# Fujin_Main.net
KiCad netlist of a schematic drawn in Altium Designer
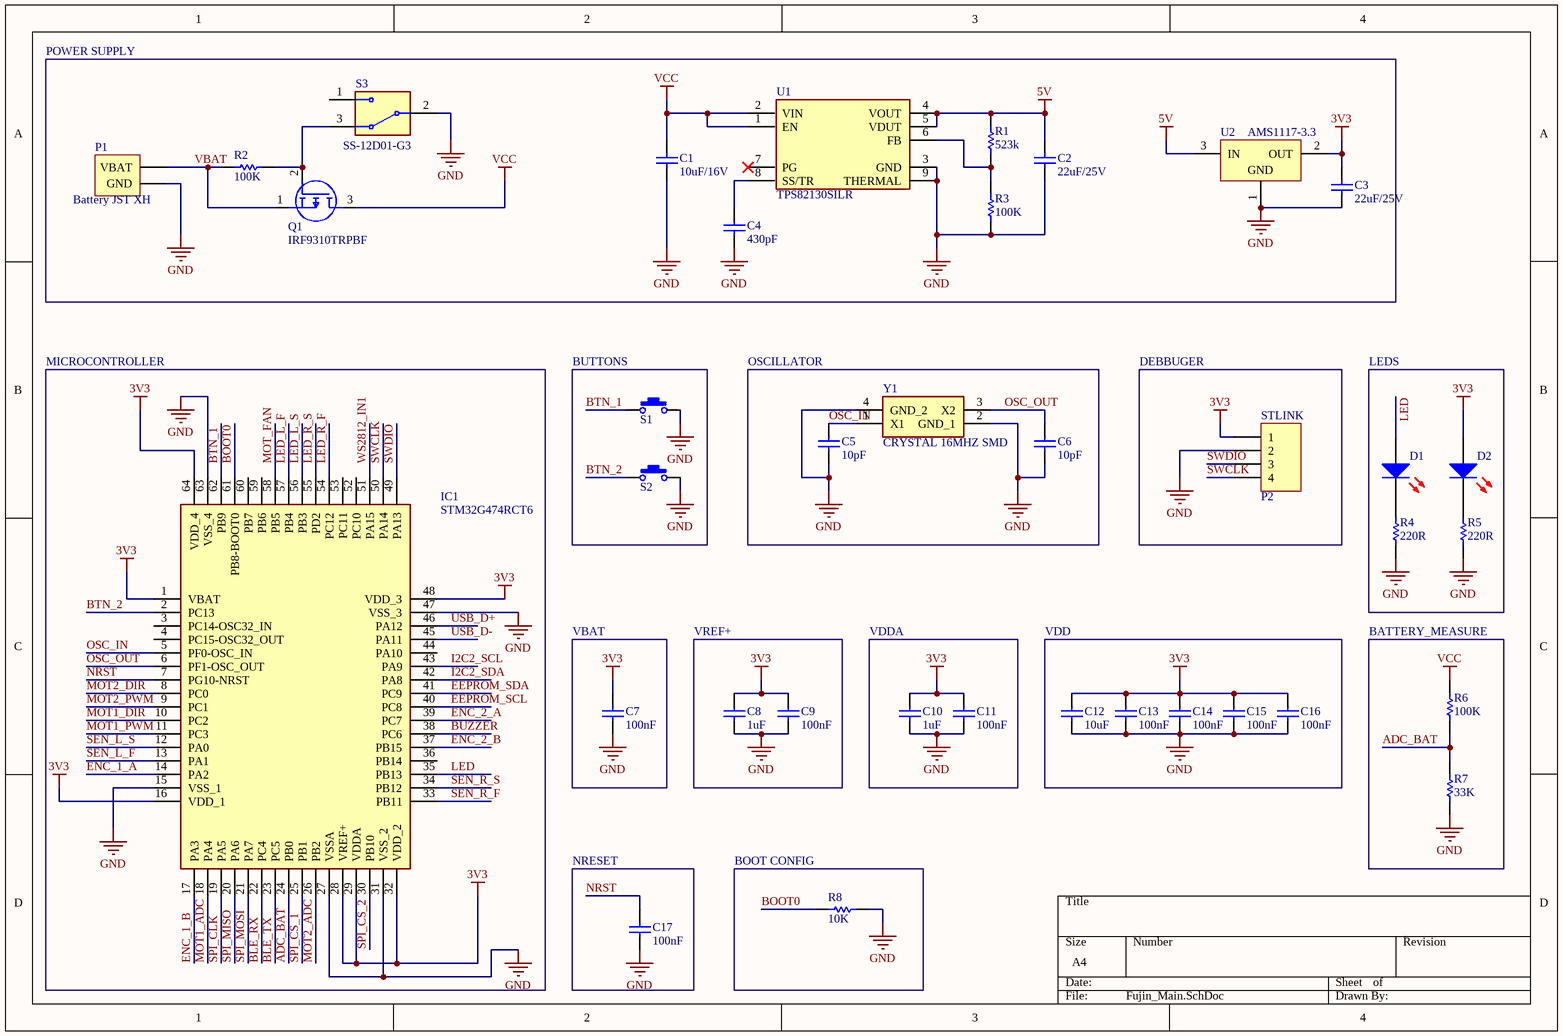
[diagram p0: Fujin_Main.SchDoc]

(export (version "E")
  (design (tool "Eeschema 10.0.6"))
  (components
    (comp (ref "C1")
      (value "10uF/16V")
      (footprint "CAPACITOR-0805")
      (description "CAP CER 10UF 16V X5R 0805")
      (fields
        (field (name "MANUFACTURER") "AVX Corporation")
        (field (name "MANUFACTURER PART NUMBER") "0805YD106KAT2A")
      )
      (libsource (lib "FujinLib") (part "CAP CER 10UF 16V X5R 0805"))
    )
    (comp (ref "C2")
      (value "22uF/25V")
      (footprint "CAPACITOR-0805")
      (description "CAP CER 22UF 25V X5R 0805")
      (fields
        (field (name "MANUFACTURER") "AVX Corporation")
        (field (name "MANUFACTURER PART NUMBER") "0805YD106KAT2A")
      )
      (libsource (lib "FujinLib") (part "CAP CER 22UF 25V X5R 0805"))
    )
    (comp (ref "C3")
      (value "22uF/25V")
      (footprint "CAPACITOR-0805")
      (description "CAP CER 22UF 25V X5R 0805")
      (fields
        (field (name "MANUFACTURER") "AVX Corporation")
        (field (name "MANUFACTURER PART NUMBER") "0805YD106KAT2A")
      )
      (libsource (lib "FujinLib") (part "CAP CER 22UF 25V X5R 0805"))
    )
    (comp (ref "C4")
      (value "430pF")
      (footprint "Capacitor-0603")
      (description "Capacitor Cer 430pF")
      (fields (field (name "MANUFACTURER PART NUMBER") "IMP14925"))
      (libsource (lib "FujinLib") (part "CAP 430pF"))
    )
    (comp (ref "C5")
      (value "10pF")
      (footprint "CAP 0402")
      (description "Capacitor Cer 10pF")
      (fields (field (name "MANUFACTURER PART NUMBER") "IMP14925"))
      (libsource (lib "FujinLib") (part "CAP 10pF"))
    )
    (comp (ref "C6")
      (value "10pF")
      (footprint "CAP 0402")
      (description "Capacitor Cer 10pF")
      (fields (field (name "MANUFACTURER PART NUMBER") "IMP14925"))
      (libsource (lib "FujinLib") (part "CAP 10pF"))
    )
    (comp (ref "C7")
      (value "100nF")
      (footprint "CAP 0402")
      (description "Capacitor Cer 100nF 50V 0402")
      (fields (field (name "MANUFACTURER PART NUMBER") "IMP14925"))
      (libsource (lib "FujinLib") (part "CAP 100NF 50V 0402"))
    )
    (comp (ref "C8")
      (value "1uF")
      (footprint "Capacitor-0603")
      (description "Multilayer Ceramic Capacitors MLCC - SMD/SMT 1uF 50Volts X5R +/-10% 0603 STD")
      (fields
        (field (name "MANUFACTURER") "Taiyo Yuden")
        (field (name "MANUFACTURER PART NUMBER") "UMK107BJ105KA-T")
      )
      (libsource (lib "FujinLib") (part "CAP CER 1UF 50V 0603"))
    )
    (comp (ref "C9")
      (value "100nF")
      (footprint "CAP 0402")
      (description "Capacitor Cer 100nF 50V 0402")
      (fields (field (name "MANUFACTURER PART NUMBER") "IMP14925"))
      (libsource (lib "FujinLib") (part "CAP 100NF 50V 0402"))
    )
    (comp (ref "C10")
      (value "1uF")
      (footprint "Capacitor-0603")
      (description "Multilayer Ceramic Capacitors MLCC - SMD/SMT 1uF 50Volts X5R +/-10% 0603 STD")
      (fields
        (field (name "MANUFACTURER") "Taiyo Yuden")
        (field (name "MANUFACTURER PART NUMBER") "UMK107BJ105KA-T")
      )
      (libsource (lib "FujinLib") (part "CAP CER 1UF 50V 0603"))
    )
    (comp (ref "C11")
      (value "100nF")
      (footprint "CAP 0402")
      (description "Capacitor Cer 100nF 50V 0402")
      (fields (field (name "MANUFACTURER PART NUMBER") "IMP14925"))
      (libsource (lib "FujinLib") (part "CAP 100NF 50V 0402"))
    )
    (comp (ref "C12")
      (value "10uF")
      (footprint "CAPACITOR-0805")
      (description "CAP CER 10UF 16V X5R 0805")
      (fields
        (field (name "MANUFACTURER") "AVX Corporation")
        (field (name "MANUFACTURER PART NUMBER") "0805YD106KAT2A")
      )
      (libsource (lib "FujinLib") (part "CAP CER 10UF 16V X5R 0805"))
    )
    (comp (ref "C13")
      (value "100nF")
      (footprint "CAP 0402")
      (description "Capacitor Cer 100nF 50V 0402")
      (fields (field (name "MANUFACTURER PART NUMBER") "IMP14925"))
      (libsource (lib "FujinLib") (part "CAP 100NF 50V 0402"))
    )
    (comp (ref "C14")
      (value "100nF")
      (footprint "CAP 0402")
      (description "Capacitor Cer 100nF 50V 0402")
      (fields (field (name "MANUFACTURER PART NUMBER") "IMP14925"))
      (libsource (lib "FujinLib") (part "CAP 100NF 50V 0402"))
    )
    (comp (ref "C15")
      (value "100nF")
      (footprint "CAP 0402")
      (description "Capacitor Cer 100nF 50V 0402")
      (fields (field (name "MANUFACTURER PART NUMBER") "IMP14925"))
      (libsource (lib "FujinLib") (part "CAP 100NF 50V 0402"))
    )
    (comp (ref "C16")
      (value "100nF")
      (footprint "CAP 0402")
      (description "Capacitor Cer 100nF 50V 0402")
      (fields (field (name "MANUFACTURER PART NUMBER") "IMP14925"))
      (libsource (lib "FujinLib") (part "CAP 100NF 50V 0402"))
    )
    (comp (ref "C17")
      (value "100nF")
      (footprint "CAP 0402")
      (description "Capacitor Cer 100nF 50V 0402")
      (fields (field (name "MANUFACTURER PART NUMBER") "IMP14925"))
      (libsource (lib "FujinLib") (part "CAP 100NF 50V 0402"))
    )
    (comp (ref "D1")
      (value "LED RED 0603")
      (footprint "LED 0603")
      (description "LED")
      (fields
        (field (name "MANUFACTURER_PART_NUMBER") "SML-D12U1WT86")
        (field (name "MOUSER PART NUMBER") "755-SML-D12U1WT86")
      )
      (libsource (lib "FujinLib") (part "LED RED 0603"))
    )
    (comp (ref "D2")
      (value "LED RED 0603")
      (footprint "LED 0603")
      (description "LED")
      (fields
        (field (name "MANUFACTURER_PART_NUMBER") "SML-D12U1WT86")
        (field (name "MOUSER PART NUMBER") "755-SML-D12U1WT86")
      )
      (libsource (lib "FujinLib") (part "LED RED 0603"))
    )
    (comp (ref "IC1")
      (value "STM32G474RCT6")
      (footprint "QFP50P1200X1200X160-64N")
      (description "Integrated Circuit")
      (fields (field (name "MOUSER PART NUMBER") "511-STM32G474RCT6"))
      (libsource (lib "FujinLib") (part "STM32G474RCT6"))
    )
    (comp (ref "P1")
      (value "Battery JST XH")
      (footprint "JST XH 1x2 Straight")
      (libsource (lib "FujinLib") (part "Battery Connector"))
    )
    (comp (ref "P2")
      (value "Header 1x4")
      (footprint "HDR MALE 1x4")
      (description "Headers & Wire Housings 40Pin 2mm Spacing Single Row Hdrs, 5pc")
      (fields (field (name "MANUFACTURER") "Cromax") (field (name "MANUFACTURER PART NUMBER") "IMP10327"))
      (libsource (lib "FujinLib") (part "Header 1x4"))
    )
    (comp (ref "Q1")
      (value "IRF9310TRPBF")
      (footprint "IRF9310TRPBF")
      (description "MOSFET (P-Channel)")
      (fields (field (name "MOUSER PART NUMBER") "942-IRF9310TRPBF"))
      (libsource (lib "FujinLib") (part "IRF9310TRPBF"))
    )
    (comp (ref "R1")
      (value "523k")
      (footprint "RESISTOR 0603")
      (libsource (lib "FujinLib") (part "RES 523K 1%"))
    )
    (comp (ref "R2")
      (value "100K")
      (footprint "RESISTOR 0603")
      (libsource (lib "FujinLib") (part "RES 100K 5%"))
    )
    (comp (ref "R3")
      (value "100K")
      (footprint "RESISTOR 0603")
      (libsource (lib "FujinLib") (part "RES 100K 1%"))
    )
    (comp (ref "R4")
      (value "220R")
      (footprint "RESISTOR 0603")
      (fields
        (field (name "MANUFACTURER") "Ty-Ohm")
        (field (name "MANUFACTURER PART NUMBER") "CR25")
        (field (name "TOLERANCE") "±5%")
      )
      (libsource (lib "FujinLib") (part "RES 220R 5%_1"))
    )
    (comp (ref "R5")
      (value "220R")
      (footprint "RESISTOR 0603")
      (fields
        (field (name "MANUFACTURER") "Ty-Ohm")
        (field (name "MANUFACTURER PART NUMBER") "CR25")
        (field (name "TOLERANCE") "±5%")
      )
      (libsource (lib "FujinLib") (part "RES 220R 5%_1"))
    )
    (comp (ref "R6")
      (value "100K")
      (footprint "RESISTOR 0603")
      (libsource (lib "FujinLib") (part "RES 100K 1%"))
    )
    (comp (ref "R7")
      (value "33K")
      (footprint "RESISTOR 0603")
      (libsource (lib "FujinLib") (part "RES 33K 1%"))
    )
    (comp (ref "R8")
      (value "10K")
      (footprint "RESISTOR 0402")
      (fields
        (field (name "MANUFACTURER") "PANASONIC ELECTRONIC COMPONENTS")
        (field (name "MANUFACTURER PART NUMBER") "ERJ-3GEYJ103V")
        (field (name "TOLERANCE") "±5%")
      )
      (libsource (lib "FujinLib") (part "RES 10K 5%"))
    )
    (comp (ref "S1")
      (value "SPST-NO")
      (footprint "B3U-1000P")
      (fields (field (name "MANUFACTURER") "Omron"))
      (libsource (lib "FujinLib") (part "Switch Tactile B3U-1000P"))
    )
    (comp (ref "S2")
      (value "SPST-NO")
      (footprint "B3U-1000P")
      (fields (field (name "MANUFACTURER") "Omron"))
      (libsource (lib "FujinLib") (part "Switch Tactile B3U-1000P"))
    )
    (comp (ref "S3")
      (value "SS-12D01-G3")
      (footprint "DEALON SS-12D01-G3")
      (description "Switch")
      (fields
        (field (name "MANUFACTURER_PART_NUMBER") "1101M2S3CGE2")
        (field (name "MOUSER PART NUMBER") "611-1101M2S3CGE2")
      )
      (libsource (lib "FujinLib") (part "1101M2S3CGE2"))
    )
    (comp (ref "U1")
      (value "TPS82130SILR")
      (footprint "SIL0008D")
      (description "Undefined or Miscellaneous")
      (fields (field (name "MOUSER PART NUMBER") "595-TPS82130SILR"))
      (libsource (lib "FujinLib") (part "TPS82130SILR"))
    )
    (comp (ref "U2")
      (value "AMS1117-3.3")
      (footprint "SOT223 - AMS1117")
      (libsource (lib "FujinLib") (part "AMS1117-3.3"))
    )
    (comp (ref "Y1")
      (value "CRYSTAL 16MHZ SMD")
      (footprint "ABM10W240000MHZ8K1ZT3")
      (description "CRYSTAL 16MHZ")
      (fields
        (field (name "MANUFACTURER_PART_NUMBER") "ABM10W-16.0000MHZ-4-B1U-T3")
        (field (name "MOUSER PART NUMBER") "815-10W16-4B1UT")
      )
      (libsource (lib "FujinLib") (part "CRYSTAL 16MHZ SMD"))
    )
  )
  (nets
    (net (code "1") (name "/ADC_BAT") (class "Default")
      (node (ref "IC1") (pin "24") (pinfunction "PB0_24") (pintype "passive"))
      (node (ref "R6") (pin "1") (pinfunction "1_1") (pintype "passive"))
      (node (ref "R7") (pin "2") (pinfunction "2_2") (pintype "passive"))
    )
    (net (code "2") (name "/BLE_RX") (class "Default")
      (node (ref "IC1") (pin "22") (pinfunction "PC4_22") (pintype "passive"))
    )
    (net (code "3") (name "/BLE_TX") (class "Default")
      (node (ref "IC1") (pin "23") (pinfunction "PC5_23") (pintype "passive"))
    )
    (net (code "4") (name "/BOOT0") (class "Default")
      (node (ref "IC1") (pin "61") (pinfunction "PB8-BOOT0_61") (pintype "passive"))
      (node (ref "R8") (pin "1") (pinfunction "1_1") (pintype "passive"))
    )
    (net (code "5") (name "/BTN_1") (class "Default")
      (node (ref "IC1") (pin "62") (pinfunction "PB9_62") (pintype "passive"))
      (node (ref "S1") (pin "1") (pinfunction "1_1") (pintype "passive"))
    )
    (net (code "6") (name "/BTN_2") (class "Default")
      (node (ref "IC1") (pin "2") (pinfunction "PC13_2") (pintype "passive"))
      (node (ref "S2") (pin "1") (pinfunction "1_1") (pintype "passive"))
    )
    (net (code "7") (name "/BUZZER") (class "Default")
      (node (ref "IC1") (pin "38") (pinfunction "PC6_38") (pintype "passive"))
    )
    (net (code "8") (name "/EEPROM_SCL") (class "Default")
      (node (ref "IC1") (pin "40") (pinfunction "PC8_40") (pintype "passive"))
    )
    (net (code "9") (name "/EEPROM_SDA") (class "Default")
      (node (ref "IC1") (pin "41") (pinfunction "PC9_41") (pintype "passive"))
    )
    (net (code "10") (name "/ENC_1_A") (class "Default")
      (node (ref "IC1") (pin "14") (pinfunction "PA2_14") (pintype "passive"))
    )
    (net (code "11") (name "/ENC_1_B") (class "Default")
      (node (ref "IC1") (pin "17") (pinfunction "PA3_17") (pintype "passive"))
    )
    (net (code "12") (name "/ENC_2_A") (class "Default")
      (node (ref "IC1") (pin "39") (pinfunction "PC7_39") (pintype "passive"))
    )
    (net (code "13") (name "/ENC_2_B") (class "Default")
      (node (ref "IC1") (pin "37") (pinfunction "PB15_37") (pintype "passive"))
    )
    (net (code "14") (name "/I2C2_SCL") (class "Default")
      (node (ref "IC1") (pin "43") (pinfunction "PA9_43") (pintype "passive"))
    )
    (net (code "15") (name "/I2C2_SDA") (class "Default")
      (node (ref "IC1") (pin "42") (pinfunction "PA8_42") (pintype "passive"))
    )
    (net (code "16") (name "/LED") (class "Default")
      (node (ref "D1") (pin "1") (pinfunction "A_1") (pintype "passive"))
      (node (ref "IC1") (pin "35") (pinfunction "PB13_35") (pintype "passive"))
    )
    (net (code "17") (name "/LED_L_F") (class "Default")
      (node (ref "IC1") (pin "57") (pinfunction "PB4_57") (pintype "passive"))
    )
    (net (code "18") (name "/LED_L_S") (class "Default")
      (node (ref "IC1") (pin "56") (pinfunction "PB3_56") (pintype "passive"))
    )
    (net (code "19") (name "/LED_R_F") (class "Default")
      (node (ref "IC1") (pin "54") (pinfunction "PC12_54") (pintype "passive"))
    )
    (net (code "20") (name "/LED_R_S") (class "Default")
      (node (ref "IC1") (pin "55") (pinfunction "PD2_55") (pintype "passive"))
    )
    (net (code "21") (name "/MOT1_ADC") (class "Default")
      (node (ref "IC1") (pin "18") (pinfunction "PA4_18") (pintype "passive"))
    )
    (net (code "22") (name "/MOT1_DIR") (class "Default")
      (node (ref "IC1") (pin "10") (pinfunction "PC2_10") (pintype "passive"))
    )
    (net (code "23") (name "/MOT1_PWM") (class "Default")
      (node (ref "IC1") (pin "11") (pinfunction "PC3_11") (pintype "passive"))
    )
    (net (code "24") (name "/MOT2_ADC") (class "Default")
      (node (ref "IC1") (pin "26") (pinfunction "PB2_26") (pintype "passive"))
    )
    (net (code "25") (name "/MOT2_DIR") (class "Default")
      (node (ref "IC1") (pin "8") (pinfunction "PC0_8") (pintype "passive"))
    )
    (net (code "26") (name "/MOT2_PWM") (class "Default")
      (node (ref "IC1") (pin "9") (pinfunction "PC1_9") (pintype "passive"))
    )
    (net (code "27") (name "/MOT_FAN") (class "Default")
      (node (ref "IC1") (pin "58") (pinfunction "PB5_58") (pintype "passive"))
    )
    (net (code "28") (name "/NRST") (class "Default")
      (node (ref "C17") (pin "2") (pinfunction "2_2") (pintype "passive"))
      (node (ref "IC1") (pin "7") (pinfunction "PG10-NRST_7") (pintype "passive"))
    )
    (net (code "29") (name "/OSC_IN") (class "Default")
      (node (ref "C5") (pin "2") (pinfunction "2_2") (pintype "passive"))
      (node (ref "IC1") (pin "5") (pinfunction "PF0-OSC_IN_5") (pintype "passive"))
      (node (ref "Y1") (pin "1") (pinfunction "X1_1") (pintype "passive"))
    )
    (net (code "30") (name "/OSC_OUT") (class "Default")
      (node (ref "C6") (pin "2") (pinfunction "2_2") (pintype "passive"))
      (node (ref "IC1") (pin "6") (pinfunction "PF1-OSC_OUT_6") (pintype "passive"))
      (node (ref "Y1") (pin "3") (pinfunction "X2_3") (pintype "passive"))
    )
    (net (code "31") (name "/SEN_L_F") (class "Default")
      (node (ref "IC1") (pin "13") (pinfunction "PA1_13") (pintype "passive"))
    )
    (net (code "32") (name "/SEN_L_S") (class "Default")
      (node (ref "IC1") (pin "12") (pinfunction "PA0_12") (pintype "passive"))
    )
    (net (code "33") (name "/SEN_R_F") (class "Default")
      (node (ref "IC1") (pin "33") (pinfunction "PB11_33") (pintype "passive"))
    )
    (net (code "34") (name "/SEN_R_S") (class "Default")
      (node (ref "IC1") (pin "34") (pinfunction "PB12_34") (pintype "passive"))
    )
    (net (code "35") (name "/SPI_CLK") (class "Default")
      (node (ref "IC1") (pin "19") (pinfunction "PA5_19") (pintype "passive"))
    )
    (net (code "36") (name "/SPI_CS_1") (class "Default")
      (node (ref "IC1") (pin "25") (pinfunction "PB1_25") (pintype "passive"))
    )
    (net (code "37") (name "/SPI_CS_2") (class "Default")
      (node (ref "IC1") (pin "30") (pinfunction "PB10_30") (pintype "passive"))
    )
    (net (code "38") (name "/SPI_MISO") (class "Default")
      (node (ref "IC1") (pin "20") (pinfunction "PA6_20") (pintype "passive"))
    )
    (net (code "39") (name "/SPI_MOSI") (class "Default")
      (node (ref "IC1") (pin "21") (pinfunction "PA7_21") (pintype "passive"))
    )
    (net (code "40") (name "/SWCLK") (class "Default")
      (node (ref "IC1") (pin "50") (pinfunction "PA14_50") (pintype "passive"))
      (node (ref "P2") (pin "4") (pinfunction "4_4") (pintype "power_in"))
    )
    (net (code "41") (name "/SWDIO") (class "Default")
      (node (ref "IC1") (pin "49") (pinfunction "PA13_49") (pintype "passive"))
      (node (ref "P2") (pin "3") (pinfunction "3_3") (pintype "power_in"))
    )
    (net (code "42") (name "/USB_D+") (class "Default")
      (node (ref "IC1") (pin "46") (pinfunction "PA12_46") (pintype "passive"))
    )
    (net (code "43") (name "/USB_D-") (class "Default")
      (node (ref "IC1") (pin "45") (pinfunction "PA11_45") (pintype "passive"))
    )
    (net (code "44") (name "/VBAT") (class "Default")
      (node (ref "P1") (pin "1") (pinfunction "VBAT_1") (pintype "power_in"))
      (node (ref "Q1") (pin "1") (pinfunction "S_1") (pintype "passive"))
      (node (ref "R2") (pin "1") (pinfunction "1_1") (pintype "passive"))
    )
    (net (code "45") (name "/WS2812_IN1") (class "Default")
      (node (ref "IC1") (pin "51") (pinfunction "PA15_51") (pintype "passive"))
    )
    (net (code "46") (name "3V3") (class "Default")
      (node (ref "C10") (pin "2") (pinfunction "2_2") (pintype "passive"))
      (node (ref "C11") (pin "2") (pinfunction "2_2") (pintype "passive"))
      (node (ref "C12") (pin "2") (pinfunction "2_2") (pintype "passive"))
      (node (ref "C13") (pin "2") (pinfunction "2_2") (pintype "passive"))
      (node (ref "C14") (pin "2") (pinfunction "2_2") (pintype "passive"))
      (node (ref "C15") (pin "2") (pinfunction "2_2") (pintype "passive"))
      (node (ref "C16") (pin "2") (pinfunction "2_2") (pintype "passive"))
      (node (ref "C3") (pin "2") (pinfunction "2_2") (pintype "passive"))
      (node (ref "C7") (pin "2") (pinfunction "2_2") (pintype "passive"))
      (node (ref "C8") (pin "2") (pinfunction "2_2") (pintype "passive"))
      (node (ref "C9") (pin "2") (pinfunction "2_2") (pintype "passive"))
      (node (ref "D2") (pin "1") (pinfunction "A_1") (pintype "passive"))
      (node (ref "IC1") (pin "1") (pinfunction "VBAT_1") (pintype "passive"))
      (node (ref "IC1") (pin "16") (pinfunction "VDD_1_16") (pintype "passive"))
      (node (ref "IC1") (pin "28") (pinfunction "VREF+_28") (pintype "passive"))
      (node (ref "IC1") (pin "29") (pinfunction "VDDA_29") (pintype "passive"))
      (node (ref "IC1") (pin "32") (pinfunction "VDD_2_32") (pintype "passive"))
      (node (ref "IC1") (pin "48") (pinfunction "VDD_3_48") (pintype "passive"))
      (node (ref "IC1") (pin "64") (pinfunction "VDD_4_64") (pintype "passive"))
      (node (ref "P2") (pin "1") (pinfunction "1_1") (pintype "passive"))
      (node (ref "U2") (pin "2") (pinfunction "OUT_2") (pintype "power_in"))
    )
    (net (code "47") (name "5V") (class "Default")
      (node (ref "C2") (pin "2") (pinfunction "2_2") (pintype "passive"))
      (node (ref "R1") (pin "2") (pinfunction "2_2") (pintype "passive"))
      (node (ref "U1") (pin "4") (pinfunction "VOUT_4") (pintype "passive"))
      (node (ref "U1") (pin "5") (pinfunction "VDUT_5") (pintype "passive"))
      (node (ref "U2") (pin "3") (pinfunction "IN_3") (pintype "power_in"))
    )
    (net (code "48") (name "GND") (class "Default")
      (node (ref "C1") (pin "1") (pinfunction "1_1") (pintype "passive"))
      (node (ref "C10") (pin "1") (pinfunction "1_1") (pintype "passive"))
      (node (ref "C11") (pin "1") (pinfunction "1_1") (pintype "passive"))
      (node (ref "C12") (pin "1") (pinfunction "1_1") (pintype "passive"))
      (node (ref "C13") (pin "1") (pinfunction "1_1") (pintype "passive"))
      (node (ref "C14") (pin "1") (pinfunction "1_1") (pintype "passive"))
      (node (ref "C15") (pin "1") (pinfunction "1_1") (pintype "passive"))
      (node (ref "C16") (pin "1") (pinfunction "1_1") (pintype "passive"))
      (node (ref "C17") (pin "1") (pinfunction "1_1") (pintype "passive"))
      (node (ref "C2") (pin "1") (pinfunction "1_1") (pintype "passive"))
      (node (ref "C3") (pin "1") (pinfunction "1_1") (pintype "passive"))
      (node (ref "C4") (pin "1") (pinfunction "1_1") (pintype "passive"))
      (node (ref "C5") (pin "1") (pinfunction "1_1") (pintype "passive"))
      (node (ref "C6") (pin "1") (pinfunction "1_1") (pintype "passive"))
      (node (ref "C7") (pin "1") (pinfunction "1_1") (pintype "passive"))
      (node (ref "C8") (pin "1") (pinfunction "1_1") (pintype "passive"))
      (node (ref "C9") (pin "1") (pinfunction "1_1") (pintype "passive"))
      (node (ref "IC1") (pin "15") (pinfunction "VSS_1_15") (pintype "passive"))
      (node (ref "IC1") (pin "27") (pinfunction "VSSA_27") (pintype "passive"))
      (node (ref "IC1") (pin "31") (pinfunction "VSS_2_31") (pintype "passive"))
      (node (ref "IC1") (pin "47") (pinfunction "VSS_3_47") (pintype "passive"))
      (node (ref "IC1") (pin "63") (pinfunction "VSS_4_63") (pintype "passive"))
      (node (ref "P1") (pin "2") (pinfunction "GND_2") (pintype "power_in"))
      (node (ref "P2") (pin "2") (pinfunction "2_2") (pintype "passive"))
      (node (ref "R3") (pin "1") (pinfunction "1_1") (pintype "passive"))
      (node (ref "R4") (pin "1") (pinfunction "1_1") (pintype "passive"))
      (node (ref "R5") (pin "1") (pinfunction "1_1") (pintype "passive"))
      (node (ref "R7") (pin "1") (pinfunction "1_1") (pintype "passive"))
      (node (ref "R8") (pin "2") (pinfunction "2_2") (pintype "passive"))
      (node (ref "S1") (pin "2") (pinfunction "2_2") (pintype "passive"))
      (node (ref "S2") (pin "2") (pinfunction "2_2") (pintype "passive"))
      (node (ref "S3") (pin "2") (pinfunction "COM_2") (pintype "passive"))
      (node (ref "U1") (pin "3") (pinfunction "GND_3") (pintype "passive"))
      (node (ref "U1") (pin "9") (pinfunction "THERMAL_9") (pintype "passive"))
      (node (ref "U2") (pin "1") (pinfunction "GND_1") (pintype "power_in"))
      (node (ref "Y1") (pin "2") (pinfunction "GND_1_2") (pintype "passive"))
      (node (ref "Y1") (pin "4") (pinfunction "GND_2_4") (pintype "passive"))
    )
    (net (code "49") (name "Net-(D1-K)") (class "Default")
      (node (ref "D1") (pin "2") (pinfunction "K_2") (pintype "passive"))
      (node (ref "R4") (pin "2") (pinfunction "2_2") (pintype "passive"))
    )
    (net (code "50") (name "Net-(D2-K)") (class "Default")
      (node (ref "D2") (pin "2") (pinfunction "K_2") (pintype "passive"))
      (node (ref "R5") (pin "2") (pinfunction "2_2") (pintype "passive"))
    )
    (net (code "51") (name "Net-(Q1-G)") (class "Default")
      (node (ref "Q1") (pin "2") (pinfunction "G_2") (pintype "passive"))
      (node (ref "R2") (pin "2") (pinfunction "2_2") (pintype "passive"))
      (node (ref "S3") (pin "3") (pinfunction "NO_3") (pintype "passive"))
    )
    (net (code "52") (name "Net-(U1-FB)") (class "Default")
      (node (ref "R1") (pin "1") (pinfunction "1_1") (pintype "passive"))
      (node (ref "R3") (pin "2") (pinfunction "2_2") (pintype "passive"))
      (node (ref "U1") (pin "6") (pinfunction "FB_6") (pintype "passive"))
    )
    (net (code "53") (name "Net-(U1-SS{slash}TR)") (class "Default")
      (node (ref "C4") (pin "2") (pinfunction "2_2") (pintype "passive"))
      (node (ref "U1") (pin "8") (pinfunction "SS/TR_8") (pintype "passive"))
    )
    (net (code "54") (name "VCC") (class "Default")
      (node (ref "C1") (pin "2") (pinfunction "2_2") (pintype "passive"))
      (node (ref "Q1") (pin "3") (pinfunction "D_3") (pintype "passive"))
      (node (ref "R6") (pin "2") (pinfunction "2_2") (pintype "passive"))
      (node (ref "U1") (pin "1") (pinfunction "EN_1") (pintype "passive"))
      (node (ref "U1") (pin "2") (pinfunction "VIN_2") (pintype "passive"))
    )
    (net (code "55") (name "unconnected-(IC1-PA10-Pad44)") (class "Default")
      (node (ref "IC1") (pin "44") (pinfunction "PA10_44") (pintype "passive"))
    )
    (net (code "56") (name "unconnected-(IC1-PB6-Pad59)") (class "Default")
      (node (ref "IC1") (pin "59") (pinfunction "PB6_59") (pintype "passive"))
    )
    (net (code "57") (name "unconnected-(IC1-PB7-Pad60)") (class "Default")
      (node (ref "IC1") (pin "60") (pinfunction "PB7_60") (pintype "passive"))
    )
    (net (code "58") (name "unconnected-(IC1-PB14-Pad36)") (class "Default")
      (node (ref "IC1") (pin "36") (pinfunction "PB14_36") (pintype "passive"))
    )
    (net (code "59") (name "unconnected-(IC1-PC10-Pad52)") (class "Default")
      (node (ref "IC1") (pin "52") (pinfunction "PC10_52") (pintype "passive"))
    )
    (net (code "60") (name "unconnected-(IC1-PC11-Pad53)") (class "Default")
      (node (ref "IC1") (pin "53") (pinfunction "PC11_53") (pintype "passive"))
    )
    (net (code "61") (name "unconnected-(IC1-PC14-OSC32_IN-Pad3)") (class "Default")
      (node (ref "IC1") (pin "3") (pinfunction "PC14-OSC32_IN_3") (pintype "passive"))
    )
    (net (code "62") (name "unconnected-(IC1-PC15-OSC32_OUT-Pad4)") (class "Default")
      (node (ref "IC1") (pin "4") (pinfunction "PC15-OSC32_OUT_4") (pintype "passive"))
    )
    (net (code "63") (name "unconnected-(S3-NC-Pad1)") (class "Default")
      (node (ref "S3") (pin "1") (pinfunction "NC_1") (pintype "passive"))
    )
    (net (code "64") (name "unconnected-(U1-PG-Pad7)") (class "Default")
      (node (ref "U1") (pin "7") (pinfunction "PG_7") (pintype "passive+no_connect"))
    )
  )
)
